# OSSIBeacon.net
KiCad netlist of a schematic drawn in EAGLE
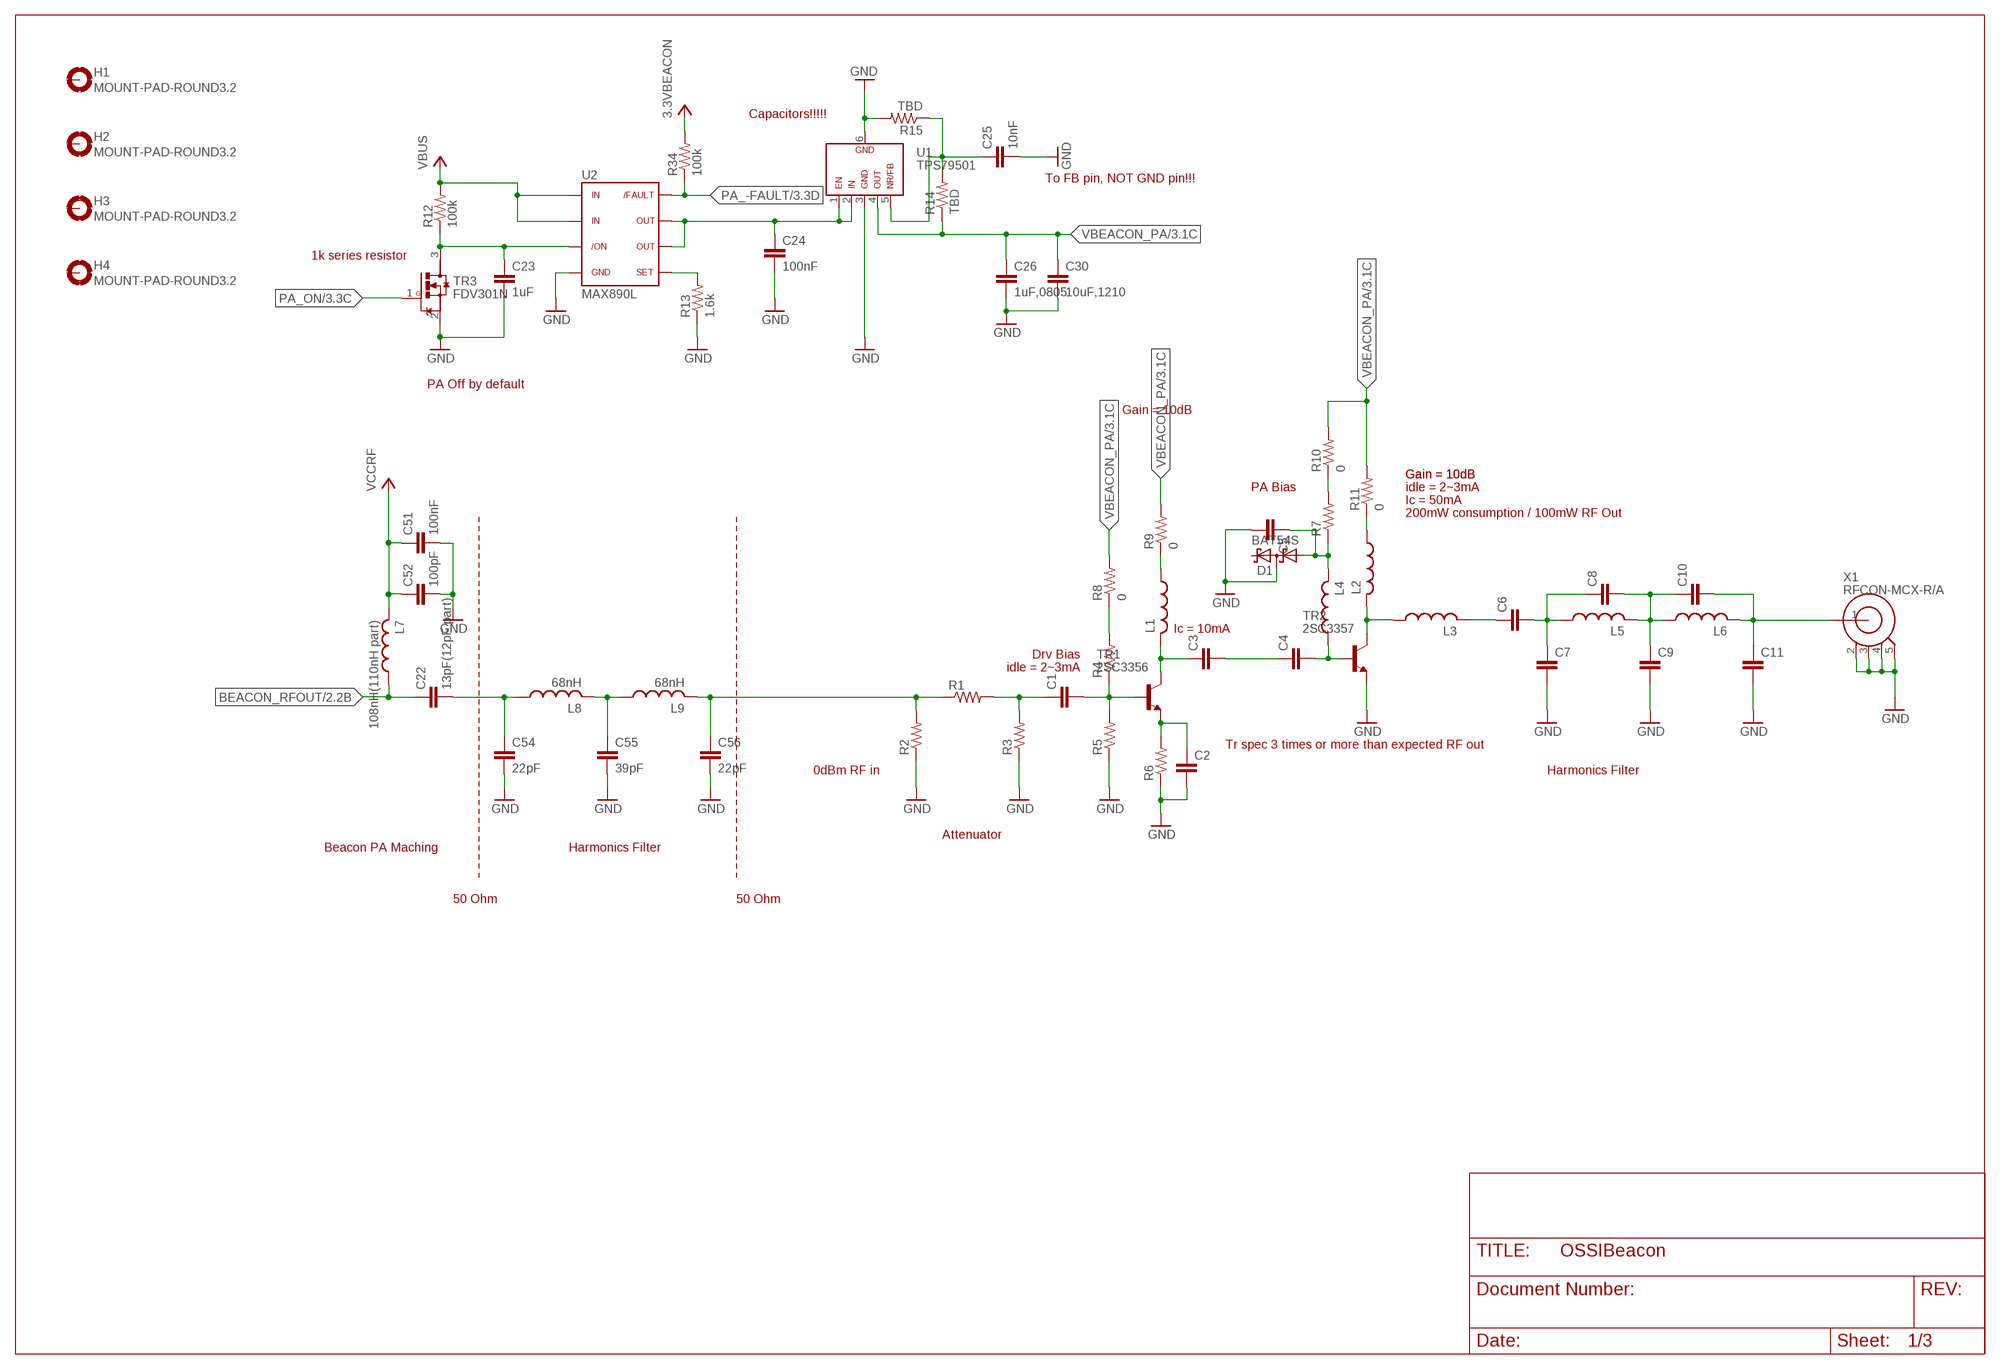
[diagram p0: schematic, sheet 1]
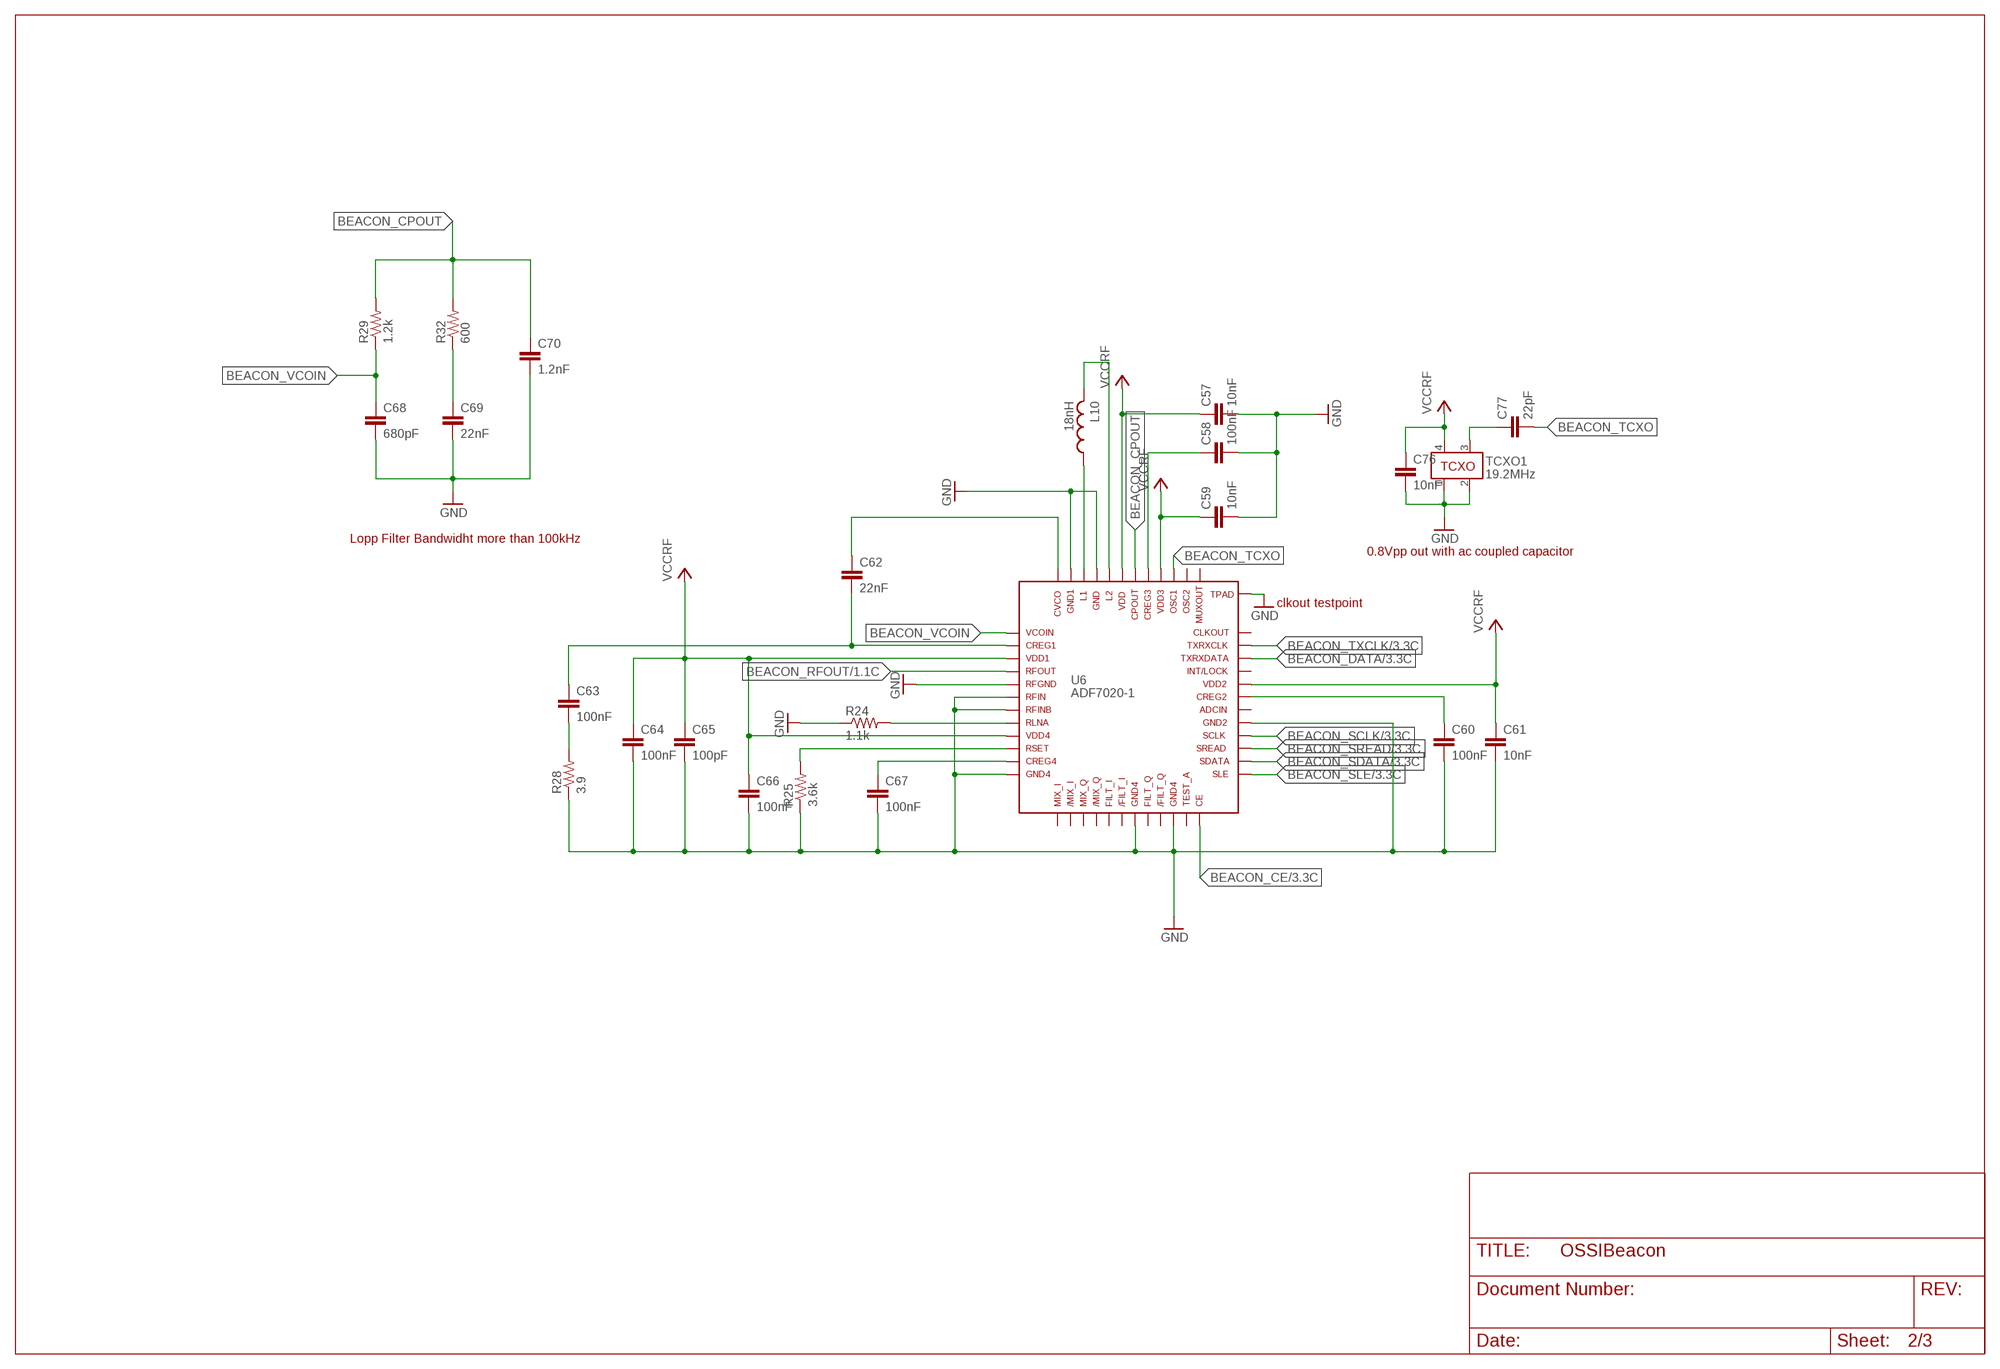
[diagram p1: schematic, sheet 2]
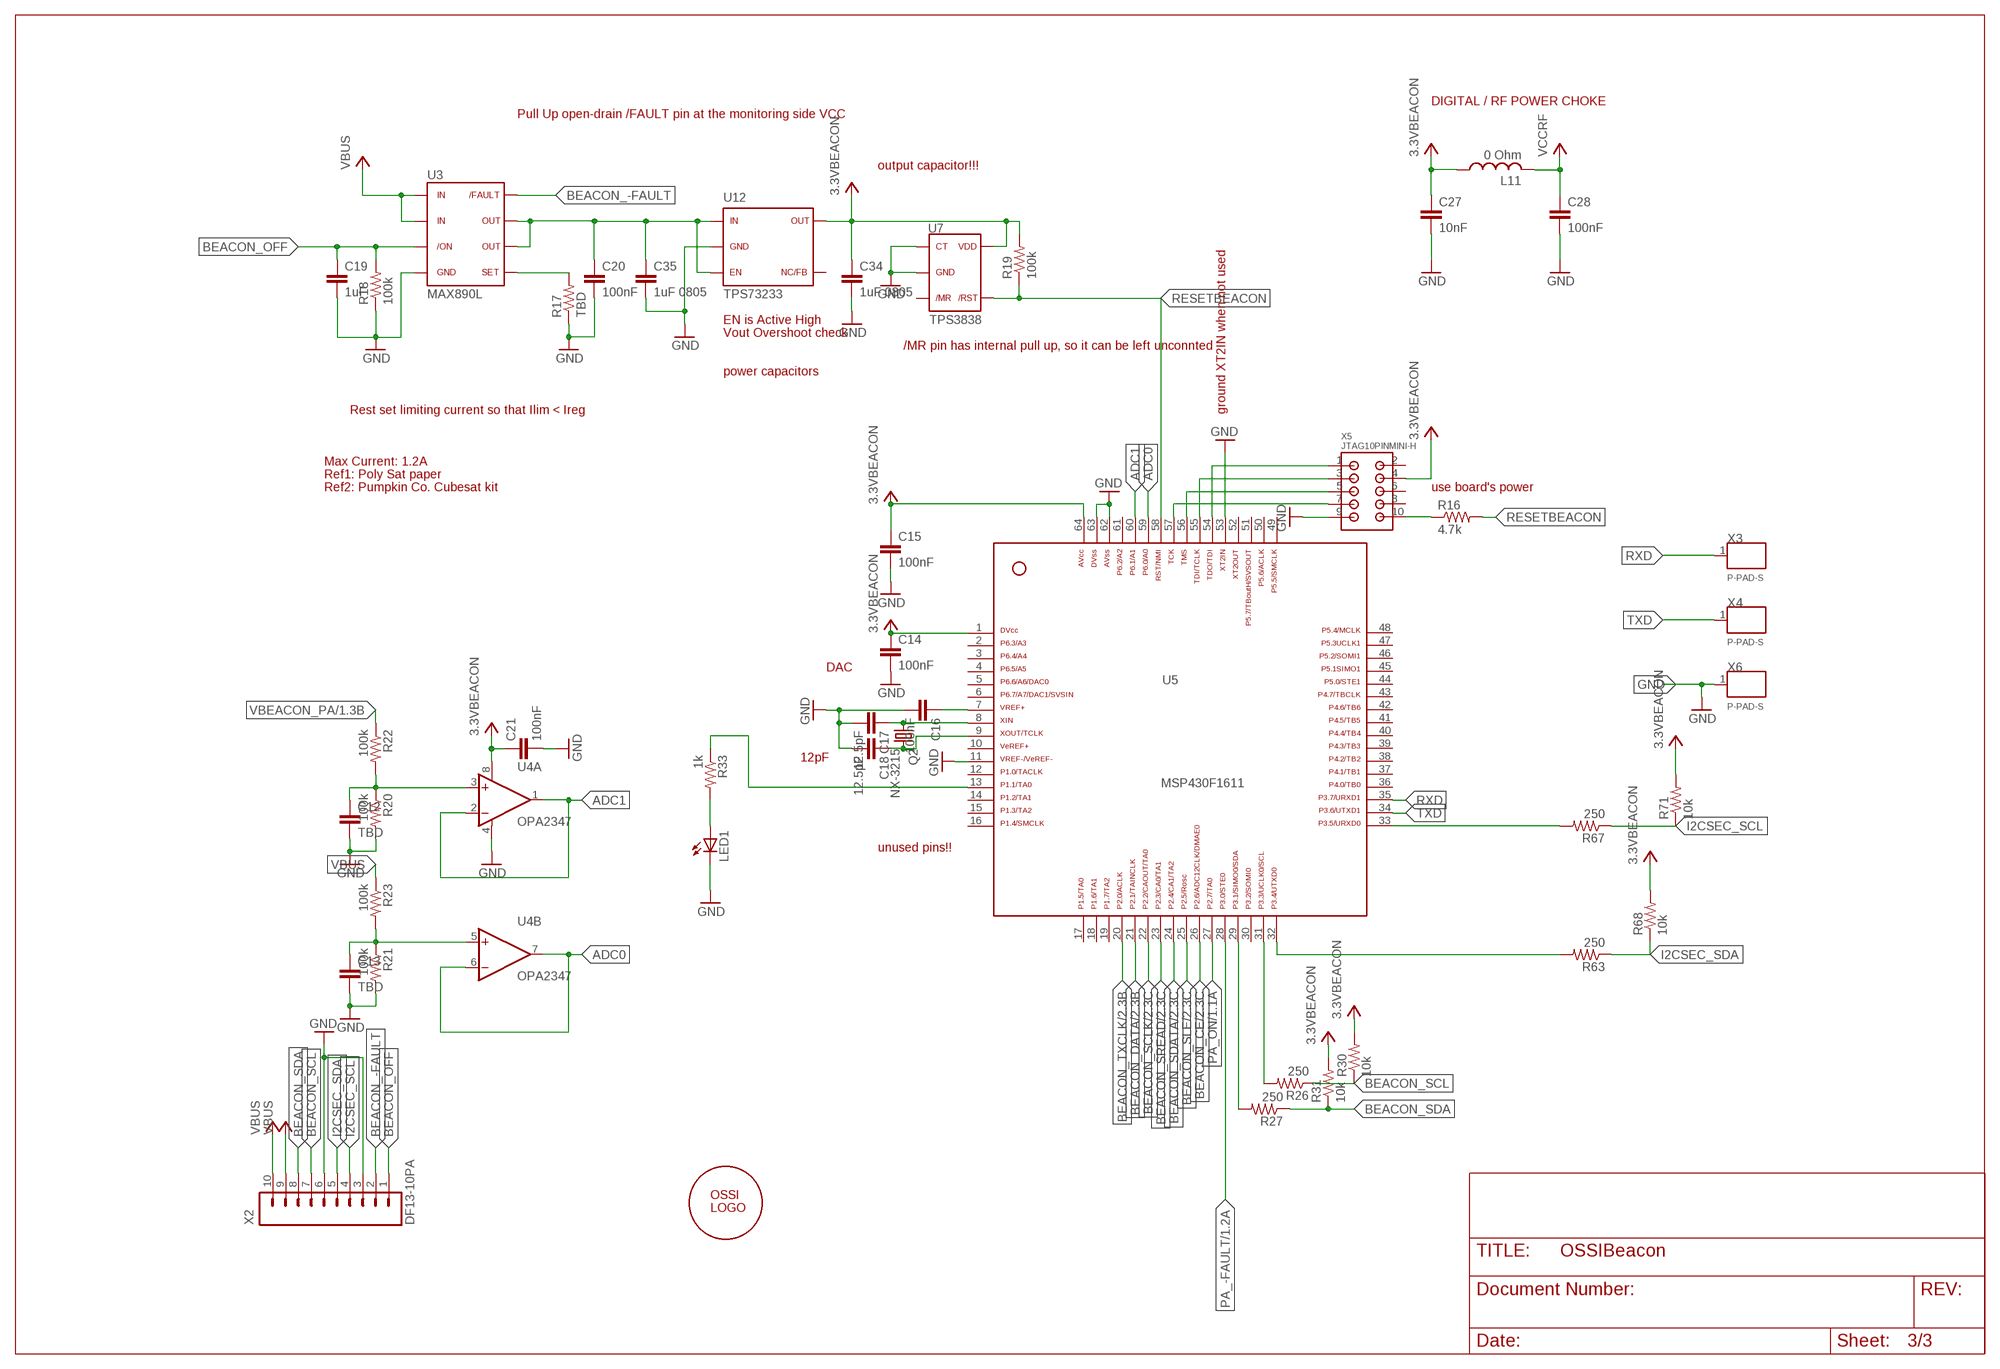
[diagram p2: schematic, sheet 3]

(export (version "E")
  (design (tool "Eeschema 10.0.6"))
  (components
    (comp (ref "C57")
      (value "10nF")
      (footprint "eagle-import:C0603(1608)")
      (libsource (lib "eagle-import") (part "C0603(1608)"))
    )
    (comp (ref "C58")
      (value "100nF")
      (footprint "eagle-import:C0603(1608)")
      (libsource (lib "eagle-import") (part "C0603(1608)"))
    )
    (comp (ref "C59")
      (value "10nF")
      (footprint "eagle-import:C0603(1608)")
      (libsource (lib "eagle-import") (part "C0603(1608)"))
    )
    (comp (ref "C60")
      (value "100nF")
      (footprint "eagle-import:C0603(1608)")
      (libsource (lib "eagle-import") (part "C0603(1608)"))
    )
    (comp (ref "C61")
      (value "10nF")
      (footprint "eagle-import:C0603(1608)")
      (libsource (lib "eagle-import") (part "C0603(1608)"))
    )
    (comp (ref "C62")
      (value "22nF")
      (footprint "eagle-import:C0603(1608)")
      (libsource (lib "eagle-import") (part "C0603(1608)"))
    )
    (comp (ref "C63")
      (value "100nF")
      (footprint "eagle-import:C0603(1608)")
      (libsource (lib "eagle-import") (part "C0603(1608)"))
    )
    (comp (ref "C64")
      (value "100nF")
      (footprint "eagle-import:C0603(1608)")
      (libsource (lib "eagle-import") (part "C0603(1608)"))
    )
    (comp (ref "C65")
      (value "100pF")
      (footprint "eagle-import:C0603(1608)")
      (libsource (lib "eagle-import") (part "C0603(1608)"))
    )
    (comp (ref "C66")
      (value "100nF")
      (footprint "eagle-import:C0603(1608)")
      (libsource (lib "eagle-import") (part "C0603(1608)"))
    )
    (comp (ref "C67")
      (value "100nF")
      (footprint "eagle-import:C0603(1608)")
      (libsource (lib "eagle-import") (part "C0603(1608)"))
    )
    (comp (ref "C68")
      (value "680pF")
      (footprint "eagle-import:C0603(1608)")
      (libsource (lib "eagle-import") (part "C0603(1608)"))
    )
    (comp (ref "C69")
      (value "22nF")
      (footprint "eagle-import:C0603(1608)")
      (libsource (lib "eagle-import") (part "C0603(1608)"))
    )
    (comp (ref "C70")
      (value "1.2nF")
      (footprint "eagle-import:C0603(1608)")
      (libsource (lib "eagle-import") (part "C0603(1608)"))
    )
    (comp (ref "C76")
      (value "10nF")
      (footprint "eagle-import:C0603(1608)")
      (libsource (lib "eagle-import") (part "C0603(1608)"))
    )
    (comp (ref "C77")
      (value "22pF")
      (footprint "eagle-import:C0603(1608)")
      (libsource (lib "eagle-import") (part "C0603(1608)"))
    )
    (comp (ref "L10")
      (value "18nH")
      (footprint "eagle-import:L0603(1608)")
      (libsource (lib "eagle-import") (part "L0603(1608)"))
    )
    (comp (ref "R24")
      (value "1.1k")
      (footprint "eagle-import:R0603(1608)")
      (libsource (lib "eagle-import") (part "R0603(1608)"))
    )
    (comp (ref "R25")
      (value "3.6k")
      (footprint "eagle-import:R0603(1608)")
      (libsource (lib "eagle-import") (part "R0603(1608)"))
    )
    (comp (ref "R28")
      (value "3.9")
      (footprint "eagle-import:R0603(1608)")
      (libsource (lib "eagle-import") (part "R0603(1608)"))
    )
    (comp (ref "R29")
      (value "1.2k")
      (footprint "eagle-import:R0603(1608)")
      (libsource (lib "eagle-import") (part "R0603(1608)"))
    )
    (comp (ref "R32")
      (value "600")
      (footprint "eagle-import:R0603(1608)")
      (libsource (lib "eagle-import") (part "R0603(1608)"))
    )
    (comp (ref "TCXO1")
      (value "19.2MHz")
      (footprint "eagle-import:TCXO_M532")
      (libsource (lib "eagle-import") (part "TCXO-M532"))
    )
    (comp (ref "U6")
      (value "ADF7020-1")
      (footprint "eagle-import:LFCSP48")
      (libsource (lib "eagle-import") (part "ADF7020-1"))
    )
    (comp (ref "C1")
      (value "C0603(1608)")
      (footprint "eagle-import:C0603(1608)")
      (libsource (lib "eagle-import") (part "C0603(1608)"))
    )
    (comp (ref "C2")
      (value "C0603(1608)")
      (footprint "eagle-import:C0603(1608)")
      (libsource (lib "eagle-import") (part "C0603(1608)"))
    )
    (comp (ref "C3")
      (value "C0603(1608)")
      (footprint "eagle-import:C0603(1608)")
      (libsource (lib "eagle-import") (part "C0603(1608)"))
    )
    (comp (ref "C4")
      (value "C0603(1608)")
      (footprint "eagle-import:C0603(1608)")
      (libsource (lib "eagle-import") (part "C0603(1608)"))
    )
    (comp (ref "C5")
      (value "C0603(1608)")
      (footprint "eagle-import:C0603(1608)")
      (libsource (lib "eagle-import") (part "C0603(1608)"))
    )
    (comp (ref "C6")
      (value "C0603(1608)")
      (footprint "eagle-import:C0603(1608)")
      (libsource (lib "eagle-import") (part "C0603(1608)"))
    )
    (comp (ref "C7")
      (value "C0603(1608)")
      (footprint "eagle-import:C0603(1608)")
      (libsource (lib "eagle-import") (part "C0603(1608)"))
    )
    (comp (ref "C8")
      (value "C0603(1608)")
      (footprint "eagle-import:C0603(1608)")
      (libsource (lib "eagle-import") (part "C0603(1608)"))
    )
    (comp (ref "C9")
      (value "C0603(1608)")
      (footprint "eagle-import:C0603(1608)")
      (libsource (lib "eagle-import") (part "C0603(1608)"))
    )
    (comp (ref "C10")
      (value "C0603(1608)")
      (footprint "eagle-import:C0603(1608)")
      (libsource (lib "eagle-import") (part "C0603(1608)"))
    )
    (comp (ref "C11")
      (value "C0603(1608)")
      (footprint "eagle-import:C0603(1608)")
      (libsource (lib "eagle-import") (part "C0603(1608)"))
    )
    (comp (ref "C22")
      (value "13pF(12pF part)")
      (footprint "eagle-import:C0603(1608)")
      (libsource (lib "eagle-import") (part "C0603(1608)"))
    )
    (comp (ref "C23")
      (value "1uF")
      (footprint "eagle-import:C0603(1608)")
      (libsource (lib "eagle-import") (part "C0603(1608)"))
    )
    (comp (ref "C24")
      (value "100nF")
      (footprint "eagle-import:C0603(1608)")
      (libsource (lib "eagle-import") (part "C0603(1608)"))
    )
    (comp (ref "C25")
      (value "10nF")
      (footprint "eagle-import:C0603(1608)")
      (libsource (lib "eagle-import") (part "C0603(1608)"))
    )
    (comp (ref "C26")
      (value "1uF,0805")
      (footprint "eagle-import:C0805(2012)")
      (libsource (lib "eagle-import") (part "C0805(2012)"))
    )
    (comp (ref "C30")
      (value "10uF,1210")
      (footprint "eagle-import:C1210-GCM32")
      (libsource (lib "eagle-import") (part "C1210(3225)-GCM32"))
    )
    (comp (ref "C51")
      (value "100nF")
      (footprint "eagle-import:C0603(1608)")
      (libsource (lib "eagle-import") (part "C0603(1608)"))
    )
    (comp (ref "C52")
      (value "100pF")
      (footprint "eagle-import:C0603(1608)")
      (libsource (lib "eagle-import") (part "C0603(1608)"))
    )
    (comp (ref "C54")
      (value "22pF")
      (footprint "eagle-import:C0603(1608)")
      (libsource (lib "eagle-import") (part "C0603(1608)"))
    )
    (comp (ref "C55")
      (value "39pF")
      (footprint "eagle-import:C0603(1608)")
      (libsource (lib "eagle-import") (part "C0603(1608)"))
    )
    (comp (ref "C56")
      (value "22pF")
      (footprint "eagle-import:C0603(1608)")
      (libsource (lib "eagle-import") (part "C0603(1608)"))
    )
    (comp (ref "D1")
      (value "BAT54S")
      (footprint "eagle-import:SOT23")
      (libsource (lib "eagle-import") (part "BAT54S"))
    )
    (comp (ref "H1")
      (value "MOUNT-PAD-ROUND3.2")
      (footprint "eagle-import:3.2-PAD-ROUND")
      (libsource (lib "eagle-import") (part "MOUNT-PAD-ROUND3.2"))
    )
    (comp (ref "H2")
      (value "MOUNT-PAD-ROUND3.2")
      (footprint "eagle-import:3.2-PAD-ROUND")
      (libsource (lib "eagle-import") (part "MOUNT-PAD-ROUND3.2"))
    )
    (comp (ref "H3")
      (value "MOUNT-PAD-ROUND3.2")
      (footprint "eagle-import:3.2-PAD-ROUND")
      (libsource (lib "eagle-import") (part "MOUNT-PAD-ROUND3.2"))
    )
    (comp (ref "H4")
      (value "MOUNT-PAD-ROUND3.2")
      (footprint "eagle-import:3.2-PAD-ROUND")
      (libsource (lib "eagle-import") (part "MOUNT-PAD-ROUND3.2"))
    )
    (comp (ref "L1")
      (value "L1008(2502)")
      (footprint "eagle-import:L1008(2520)")
      (libsource (lib "eagle-import") (part "L1008(2502)"))
    )
    (comp (ref "L2")
      (value "L1008(2502)")
      (footprint "eagle-import:L1008(2520)")
      (libsource (lib "eagle-import") (part "L1008(2502)"))
    )
    (comp (ref "L3")
      (value "L0603(1608)")
      (footprint "eagle-import:L0603(1608)")
      (libsource (lib "eagle-import") (part "L0603(1608)"))
    )
    (comp (ref "L4")
      (value "L0603(1608)")
      (footprint "eagle-import:L0603(1608)")
      (libsource (lib "eagle-import") (part "L0603(1608)"))
    )
    (comp (ref "L5")
      (value "L0603(1608)")
      (footprint "eagle-import:L0603(1608)")
      (libsource (lib "eagle-import") (part "L0603(1608)"))
    )
    (comp (ref "L6")
      (value "L0603(1608)")
      (footprint "eagle-import:L0603(1608)")
      (libsource (lib "eagle-import") (part "L0603(1608)"))
    )
    (comp (ref "L7")
      (value "108nH(110nH part)")
      (footprint "eagle-import:L0603(1608)")
      (libsource (lib "eagle-import") (part "L0603(1608)"))
    )
    (comp (ref "L8")
      (value "68nH")
      (footprint "eagle-import:L0603(1608)")
      (libsource (lib "eagle-import") (part "L0603(1608)"))
    )
    (comp (ref "L9")
      (value "68nH")
      (footprint "eagle-import:L0603(1608)")
      (libsource (lib "eagle-import") (part "L0603(1608)"))
    )
    (comp (ref "R1")
      (value "R0603(1608)")
      (footprint "eagle-import:R0603(1608)")
      (libsource (lib "eagle-import") (part "R0603(1608)"))
    )
    (comp (ref "R2")
      (value "R0603(1608)")
      (footprint "eagle-import:R0603(1608)")
      (libsource (lib "eagle-import") (part "R0603(1608)"))
    )
    (comp (ref "R3")
      (value "R0603(1608)")
      (footprint "eagle-import:R0603(1608)")
      (libsource (lib "eagle-import") (part "R0603(1608)"))
    )
    (comp (ref "R4")
      (value "R0603(1608)")
      (footprint "eagle-import:R0603(1608)")
      (libsource (lib "eagle-import") (part "R0603(1608)"))
    )
    (comp (ref "R5")
      (value "R0603(1608)")
      (footprint "eagle-import:R0603(1608)")
      (libsource (lib "eagle-import") (part "R0603(1608)"))
    )
    (comp (ref "R6")
      (value "R0603(1608)")
      (footprint "eagle-import:R0603(1608)")
      (libsource (lib "eagle-import") (part "R0603(1608)"))
    )
    (comp (ref "R7")
      (value "R0603(1608)")
      (footprint "eagle-import:R0603(1608)")
      (libsource (lib "eagle-import") (part "R0603(1608)"))
    )
    (comp (ref "R8")
      (value "0")
      (footprint "eagle-import:R0603(1608)")
      (libsource (lib "eagle-import") (part "R0603(1608)"))
    )
    (comp (ref "R9")
      (value "0")
      (footprint "eagle-import:R0603(1608)")
      (libsource (lib "eagle-import") (part "R0603(1608)"))
    )
    (comp (ref "R10")
      (value "0")
      (footprint "eagle-import:R0603(1608)")
      (libsource (lib "eagle-import") (part "R0603(1608)"))
    )
    (comp (ref "R11")
      (value "0")
      (footprint "eagle-import:R0603(1608)")
      (libsource (lib "eagle-import") (part "R0603(1608)"))
    )
    (comp (ref "R12")
      (value "100k")
      (footprint "eagle-import:R0603(1608)")
      (libsource (lib "eagle-import") (part "R0603(1608)"))
    )
    (comp (ref "R13")
      (value "1.6k")
      (footprint "eagle-import:R0603(1608)")
      (libsource (lib "eagle-import") (part "R0603(1608)"))
    )
    (comp (ref "R14")
      (value "TBD")
      (footprint "eagle-import:R0603(1608)")
      (libsource (lib "eagle-import") (part "R0603(1608)"))
    )
    (comp (ref "R15")
      (value "TBD")
      (footprint "eagle-import:R0603(1608)")
      (libsource (lib "eagle-import") (part "R0603(1608)"))
    )
    (comp (ref "R34")
      (value "100k")
      (footprint "eagle-import:R0603(1608)")
      (libsource (lib "eagle-import") (part "R0603(1608)"))
    )
    (comp (ref "TR1")
      (value "2SC3356")
      (footprint "eagle-import:SOT23-BEC")
      (libsource (lib "eagle-import") (part "2SC3356"))
    )
    (comp (ref "TR2")
      (value "2SC3357")
      (footprint "eagle-import:SOT89-R")
      (libsource (lib "eagle-import") (part "2SC3357"))
    )
    (comp (ref "TR3")
      (value "FDV301N")
      (footprint "eagle-import:SOT23")
      (libsource (lib "eagle-import") (part "FDV301N"))
    )
    (comp (ref "U1")
      (value "TPS79501")
      (footprint "eagle-import:SOT223-6")
      (libsource (lib "eagle-import") (part "TPS79501"))
    )
    (comp (ref "U2")
      (value "MAX890L")
      (footprint "eagle-import:SO8")
      (libsource (lib "eagle-import") (part "MAX890L"))
    )
    (comp (ref "X1")
      (value "RFCON-MCX-R/A")
      (footprint "eagle-import:MCX-R_A")
      (libsource (lib "eagle-import") (part "RFCON-MCX-R/A"))
    )
    (comp (ref "C12")
      (value "TBD")
      (footprint "eagle-import:C0603(1608)")
      (libsource (lib "eagle-import") (part "C0603(1608)"))
    )
    (comp (ref "C13")
      (value "TBD")
      (footprint "eagle-import:C0603(1608)")
      (libsource (lib "eagle-import") (part "C0603(1608)"))
    )
    (comp (ref "C14")
      (value "100nF")
      (footprint "eagle-import:C0603(1608)")
      (libsource (lib "eagle-import") (part "C0603(1608)"))
    )
    (comp (ref "C15")
      (value "100nF")
      (footprint "eagle-import:C0603(1608)")
      (libsource (lib "eagle-import") (part "C0603(1608)"))
    )
    (comp (ref "C16")
      (value "100nF")
      (footprint "eagle-import:C0603(1608)")
      (libsource (lib "eagle-import") (part "C0603(1608)"))
    )
    (comp (ref "C17")
      (value "12.5pF")
      (footprint "eagle-import:C0603(1608)")
      (libsource (lib "eagle-import") (part "C0603(1608)"))
    )
    (comp (ref "C18")
      (value "12.5pF")
      (footprint "eagle-import:C0603(1608)")
      (libsource (lib "eagle-import") (part "C0603(1608)"))
    )
    (comp (ref "C19")
      (value "1uF")
      (footprint "eagle-import:C0603(1608)")
      (libsource (lib "eagle-import") (part "C0603(1608)"))
    )
    (comp (ref "C20")
      (value "100nF")
      (footprint "eagle-import:C0603(1608)")
      (libsource (lib "eagle-import") (part "C0603(1608)"))
    )
    (comp (ref "C21")
      (value "100nF")
      (footprint "eagle-import:C0603(1608)")
      (libsource (lib "eagle-import") (part "C0603(1608)"))
    )
    (comp (ref "C27")
      (value "10nF")
      (footprint "eagle-import:C0603(1608)")
      (libsource (lib "eagle-import") (part "C0603(1608)"))
    )
    (comp (ref "C28")
      (value "100nF")
      (footprint "eagle-import:C0603(1608)")
      (libsource (lib "eagle-import") (part "C0603(1608)"))
    )
    (comp (ref "C34")
      (value "1uF 0805")
      (footprint "eagle-import:C0805(2012)")
      (libsource (lib "eagle-import") (part "C0805(2012)"))
    )
    (comp (ref "C35")
      (value "1uF 0805")
      (footprint "eagle-import:C0805(2012)")
      (libsource (lib "eagle-import") (part "C0805(2012)"))
    )
    (comp (ref "L11")
      (value "0 Ohm")
      (footprint "eagle-import:L0805(2012)")
      (libsource (lib "eagle-import") (part "L0805(2012)"))
    )
    (comp (ref "LED1")
      (value "LED0603")
      (footprint "eagle-import:LED-0603")
      (libsource (lib "eagle-import") (part "LED0603"))
    )
    (comp (ref "Q2")
      (value "NX-3215")
      (footprint "eagle-import:NX-3215")
      (libsource (lib "eagle-import") (part "NX-3215"))
    )
    (comp (ref "R16")
      (value "4.7k")
      (footprint "eagle-import:R0603(1608)")
      (libsource (lib "eagle-import") (part "R0603(1608)"))
    )
    (comp (ref "R17")
      (value "TBD")
      (footprint "eagle-import:R0603(1608)")
      (libsource (lib "eagle-import") (part "R0603(1608)"))
    )
    (comp (ref "R18")
      (value "100k")
      (footprint "eagle-import:R0603(1608)")
      (libsource (lib "eagle-import") (part "R0603(1608)"))
    )
    (comp (ref "R19")
      (value "100k")
      (footprint "eagle-import:R0603(1608)")
      (libsource (lib "eagle-import") (part "R0603(1608)"))
    )
    (comp (ref "R20")
      (value "100k")
      (footprint "eagle-import:R0603(1608)")
      (libsource (lib "eagle-import") (part "R0603(1608)"))
    )
    (comp (ref "R21")
      (value "100k")
      (footprint "eagle-import:R0603(1608)")
      (libsource (lib "eagle-import") (part "R0603(1608)"))
    )
    (comp (ref "R22")
      (value "100k")
      (footprint "eagle-import:R0603(1608)")
      (libsource (lib "eagle-import") (part "R0603(1608)"))
    )
    (comp (ref "R23")
      (value "100k")
      (footprint "eagle-import:R0603(1608)")
      (libsource (lib "eagle-import") (part "R0603(1608)"))
    )
    (comp (ref "R26")
      (value "250")
      (footprint "eagle-import:R0603(1608)")
      (libsource (lib "eagle-import") (part "R0603(1608)"))
    )
    (comp (ref "R27")
      (value "250")
      (footprint "eagle-import:R0603(1608)")
      (libsource (lib "eagle-import") (part "R0603(1608)"))
    )
    (comp (ref "R30")
      (value "10k")
      (footprint "eagle-import:R0603(1608)")
      (libsource (lib "eagle-import") (part "R0603(1608)"))
    )
    (comp (ref "R31")
      (value "10k")
      (footprint "eagle-import:R0603(1608)")
      (libsource (lib "eagle-import") (part "R0603(1608)"))
    )
    (comp (ref "R33")
      (value "1k")
      (footprint "eagle-import:R0603(1608)")
      (libsource (lib "eagle-import") (part "R0603(1608)"))
    )
    (comp (ref "R63")
      (value "250")
      (footprint "eagle-import:R0603(1608)")
      (libsource (lib "eagle-import") (part "R0603(1608)"))
    )
    (comp (ref "R67")
      (value "250")
      (footprint "eagle-import:R0603(1608)")
      (libsource (lib "eagle-import") (part "R0603(1608)"))
    )
    (comp (ref "R68")
      (value "10k")
      (footprint "eagle-import:R0603(1608)")
      (libsource (lib "eagle-import") (part "R0603(1608)"))
    )
    (comp (ref "R71")
      (value "10k")
      (footprint "eagle-import:R0603(1608)")
      (libsource (lib "eagle-import") (part "R0603(1608)"))
    )
    (comp (ref "U$1")
      (value "OSSILOGORECT")
      (footprint "eagle-import:OSSILOGORECT1005")
      (libsource (lib "eagle-import") (part "OSSILOGORECT"))
    )
    (comp (ref "U3")
      (value "MAX890L")
      (footprint "eagle-import:SO8")
      (libsource (lib "eagle-import") (part "MAX890L"))
    )
    (comp (ref "U4")
      (value "OPA2347")
      (footprint "eagle-import:SOT23-8DCN")
      (libsource (lib "eagle-import") (part "OPA2347"))
    )
    (comp (ref "U5")
      (value "MSP430F1611")
      (footprint "eagle-import:PM_PAG64")
      (libsource (lib "eagle-import") (part "MSP430F1611"))
    )
    (comp (ref "U7")
      (value "TPS3838")
      (footprint "eagle-import:SOT23-5DBV")
      (libsource (lib "eagle-import") (part "TPS3838"))
    )
    (comp (ref "U12")
      (value "TPS73233")
      (footprint "eagle-import:SOT23-5DBV")
      (libsource (lib "eagle-import") (part "TPS73233"))
    )
    (comp (ref "X2")
      (value "DF13-10PA")
      (footprint "eagle-import:DF13A-10P")
      (libsource (lib "eagle-import") (part "DF13-10PA"))
    )
    (comp (ref "X3")
      (value "P-PAD-S")
      (footprint "eagle-import:P-PAD-S")
      (libsource (lib "eagle-import") (part "P-PAD-S"))
    )
    (comp (ref "X4")
      (value "P-PAD-S")
      (footprint "eagle-import:P-PAD-S")
      (libsource (lib "eagle-import") (part "P-PAD-S"))
    )
    (comp (ref "X5")
      (value "JTAG10PINMINI-H")
      (footprint "eagle-import:M50-3200545")
      (libsource (lib "eagle-import") (part "JTAG10PINMINI-H"))
    )
    (comp (ref "X6")
      (value "P-PAD-S")
      (footprint "eagle-import:P-PAD-S")
      (libsource (lib "eagle-import") (part "P-PAD-S"))
    )
  )
  (nets
    (net (code "1") (name "3.3VBEACON") (class "Default")
      (node (ref "C14") (pin "1") (pinfunction "1_1") (pintype "passive"))
      (node (ref "C15") (pin "1") (pinfunction "1_1") (pintype "passive"))
      (node (ref "C21") (pin "1") (pinfunction "1_1") (pintype "passive"))
      (node (ref "C27") (pin "1") (pinfunction "1_1") (pintype "passive"))
      (node (ref "C34") (pin "1") (pinfunction "1_1") (pintype "passive"))
      (node (ref "L11") (pin "1") (pinfunction "1_1") (pintype "passive"))
      (node (ref "R19") (pin "2") (pinfunction "2_2") (pintype "passive"))
      (node (ref "R30") (pin "2") (pinfunction "2_2") (pintype "passive"))
      (node (ref "R31") (pin "2") (pinfunction "2_2") (pintype "passive"))
      (node (ref "R34") (pin "2") (pinfunction "2_2") (pintype "passive"))
      (node (ref "R68") (pin "2") (pinfunction "2_2") (pintype "passive"))
      (node (ref "R71") (pin "2") (pinfunction "2_2") (pintype "passive"))
      (node (ref "U12") (pin "5") (pinfunction "5_5") (pintype "power_in"))
      (node (ref "U4") (pin "8") (pinfunction "V+_8") (pintype "power_in"))
      (node (ref "U5") (pin "1") (pinfunction "1_1") (pintype "power_in"))
      (node (ref "U5") (pin "64") (pinfunction "64_64") (pintype "power_in"))
      (node (ref "U7") (pin "5") (pinfunction "P$5_5") (pintype "power_in"))
      (node (ref "X5") (pin "4") (pinfunction "4_4") (pintype "bidirectional"))
    )
    (net (code "2") (name "ADC0") (class "Default")
      (node (ref "U4") (pin "6") (pinfunction "-IN_6") (pintype "input"))
      (node (ref "U4") (pin "7") (pinfunction "OUT_7") (pintype "output"))
      (node (ref "U5") (pin "59") (pinfunction "59_59") (pintype "bidirectional"))
    )
    (net (code "3") (name "ADC1") (class "Default")
      (node (ref "U4") (pin "1") (pinfunction "OUT_1") (pintype "output"))
      (node (ref "U4") (pin "2") (pinfunction "-IN_2") (pintype "input"))
      (node (ref "U5") (pin "60") (pinfunction "60_60") (pintype "bidirectional"))
    )
    (net (code "4") (name "BEACON_-FAULT") (class "Default")
      (node (ref "U3") (pin "8") (pinfunction "P$8_8") (pintype "output"))
      (node (ref "X2") (pin "2") (pinfunction "2_2") (pintype "passive"))
    )
    (net (code "5") (name "BEACON_CE") (class "Default")
      (node (ref "U5") (pin "26") (pinfunction "26_26") (pintype "bidirectional"))
      (node (ref "U6") (pin "24") (pinfunction "P$24_24") (pintype "bidirectional"))
    )
    (net (code "6") (name "BEACON_CPOUT") (class "Default")
      (node (ref "C70") (pin "1") (pinfunction "1_1") (pintype "passive"))
      (node (ref "R29") (pin "2") (pinfunction "2_2") (pintype "passive"))
      (node (ref "R32") (pin "2") (pinfunction "2_2") (pintype "passive"))
      (node (ref "U6") (pin "42") (pinfunction "P$42_42") (pintype "bidirectional"))
    )
    (net (code "7") (name "BEACON_DATA") (class "Default")
      (node (ref "U5") (pin "21") (pinfunction "21_21") (pintype "bidirectional"))
      (node (ref "U6") (pin "34") (pinfunction "P$34_34") (pintype "bidirectional"))
    )
    (net (code "8") (name "BEACON_OFF") (class "Default")
      (node (ref "C19") (pin "1") (pinfunction "1_1") (pintype "passive"))
      (node (ref "R18") (pin "2") (pinfunction "2_2") (pintype "passive"))
      (node (ref "U3") (pin "3") (pinfunction "P$3_3") (pintype "input"))
      (node (ref "X2") (pin "1") (pinfunction "1_1") (pintype "passive"))
    )
    (net (code "9") (name "BEACON_RFOUT") (class "Default")
      (node (ref "C22") (pin "1") (pinfunction "1_1") (pintype "passive"))
      (node (ref "L7") (pin "1") (pinfunction "1_1") (pintype "passive"))
      (node (ref "U6") (pin "4") (pinfunction "P$4_4") (pintype "bidirectional"))
    )
    (net (code "10") (name "BEACON_SCL") (class "Default")
      (node (ref "R26") (pin "1") (pinfunction "1_1") (pintype "passive"))
      (node (ref "R30") (pin "1") (pinfunction "1_1") (pintype "passive"))
      (node (ref "X2") (pin "7") (pinfunction "7_7") (pintype "passive"))
    )
    (net (code "11") (name "BEACON_SCLK") (class "Default")
      (node (ref "U5") (pin "22") (pinfunction "22_22") (pintype "bidirectional"))
      (node (ref "U6") (pin "28") (pinfunction "P$28_28") (pintype "bidirectional"))
    )
    (net (code "12") (name "BEACON_SDA") (class "Default")
      (node (ref "R27") (pin "1") (pinfunction "1_1") (pintype "passive"))
      (node (ref "R31") (pin "1") (pinfunction "1_1") (pintype "passive"))
      (node (ref "X2") (pin "8") (pinfunction "8_8") (pintype "passive"))
    )
    (net (code "13") (name "BEACON_SDATA") (class "Default")
      (node (ref "U5") (pin "24") (pinfunction "24_24") (pintype "bidirectional"))
      (node (ref "U6") (pin "26") (pinfunction "P$26_26") (pintype "bidirectional"))
    )
    (net (code "14") (name "BEACON_SLE") (class "Default")
      (node (ref "U5") (pin "25") (pinfunction "25_25") (pintype "bidirectional"))
      (node (ref "U6") (pin "25") (pinfunction "P$25_25") (pintype "bidirectional"))
    )
    (net (code "15") (name "BEACON_SREAD") (class "Default")
      (node (ref "U5") (pin "23") (pinfunction "23_23") (pintype "bidirectional"))
      (node (ref "U6") (pin "27") (pinfunction "P$27_27") (pintype "bidirectional"))
    )
    (net (code "16") (name "BEACON_TCXO") (class "Default")
      (node (ref "C77") (pin "2") (pinfunction "2_2") (pintype "passive"))
      (node (ref "U6") (pin "39") (pinfunction "P$39_39") (pintype "bidirectional"))
    )
    (net (code "17") (name "BEACON_TXCLK") (class "Default")
      (node (ref "U5") (pin "20") (pinfunction "20_20") (pintype "bidirectional"))
      (node (ref "U6") (pin "35") (pinfunction "P$35_35") (pintype "bidirectional"))
    )
    (net (code "18") (name "BEACON_VCOIN") (class "Default")
      (node (ref "C68") (pin "1") (pinfunction "1_1") (pintype "passive"))
      (node (ref "R29") (pin "1") (pinfunction "1_1") (pintype "passive"))
      (node (ref "U6") (pin "1") (pinfunction "P$1_1") (pintype "bidirectional"))
    )
    (net (code "19") (name "GND") (class "Default")
      (node (ref "C11") (pin "2") (pinfunction "2_2") (pintype "passive"))
      (node (ref "C12") (pin "2") (pinfunction "2_2") (pintype "passive"))
      (node (ref "C13") (pin "2") (pinfunction "2_2") (pintype "passive"))
      (node (ref "C14") (pin "2") (pinfunction "2_2") (pintype "passive"))
      (node (ref "C15") (pin "2") (pinfunction "2_2") (pintype "passive"))
      (node (ref "C16") (pin "2") (pinfunction "2_2") (pintype "passive"))
      (node (ref "C17") (pin "2") (pinfunction "2_2") (pintype "passive"))
      (node (ref "C18") (pin "2") (pinfunction "2_2") (pintype "passive"))
      (node (ref "C19") (pin "2") (pinfunction "2_2") (pintype "passive"))
      (node (ref "C2") (pin "2") (pinfunction "2_2") (pintype "passive"))
      (node (ref "C20") (pin "2") (pinfunction "2_2") (pintype "passive"))
      (node (ref "C21") (pin "2") (pinfunction "2_2") (pintype "passive"))
      (node (ref "C23") (pin "2") (pinfunction "2_2") (pintype "passive"))
      (node (ref "C24") (pin "2") (pinfunction "2_2") (pintype "passive"))
      (node (ref "C25") (pin "2") (pinfunction "2_2") (pintype "passive"))
      (node (ref "C26") (pin "2") (pinfunction "2_2") (pintype "passive"))
      (node (ref "C27") (pin "2") (pinfunction "2_2") (pintype "passive"))
      (node (ref "C28") (pin "2") (pinfunction "2_2") (pintype "passive"))
      (node (ref "C30") (pin "P$2") (pinfunction "2_P$2") (pintype "passive"))
      (node (ref "C34") (pin "2") (pinfunction "2_2") (pintype "passive"))
      (node (ref "C35") (pin "2") (pinfunction "2_2") (pintype "passive"))
      (node (ref "C5") (pin "2") (pinfunction "2_2") (pintype "passive"))
      (node (ref "C51") (pin "2") (pinfunction "2_2") (pintype "passive"))
      (node (ref "C52") (pin "2") (pinfunction "2_2") (pintype "passive"))
      (node (ref "C54") (pin "2") (pinfunction "2_2") (pintype "passive"))
      (node (ref "C55") (pin "2") (pinfunction "2_2") (pintype "passive"))
      (node (ref "C56") (pin "2") (pinfunction "2_2") (pintype "passive"))
      (node (ref "C57") (pin "2") (pinfunction "2_2") (pintype "passive"))
      (node (ref "C58") (pin "2") (pinfunction "2_2") (pintype "passive"))
      (node (ref "C59") (pin "2") (pinfunction "2_2") (pintype "passive"))
      (node (ref "C60") (pin "2") (pinfunction "2_2") (pintype "passive"))
      (node (ref "C61") (pin "2") (pinfunction "2_2") (pintype "passive"))
      (node (ref "C64") (pin "2") (pinfunction "2_2") (pintype "passive"))
      (node (ref "C65") (pin "2") (pinfunction "2_2") (pintype "passive"))
      (node (ref "C66") (pin "2") (pinfunction "2_2") (pintype "passive"))
      (node (ref "C67") (pin "2") (pinfunction "2_2") (pintype "passive"))
      (node (ref "C68") (pin "2") (pinfunction "2_2") (pintype "passive"))
      (node (ref "C69") (pin "2") (pinfunction "2_2") (pintype "passive"))
      (node (ref "C7") (pin "2") (pinfunction "2_2") (pintype "passive"))
      (node (ref "C70") (pin "2") (pinfunction "2_2") (pintype "passive"))
      (node (ref "C76") (pin "2") (pinfunction "2_2") (pintype "passive"))
      (node (ref "C9") (pin "2") (pinfunction "2_2") (pintype "passive"))
      (node (ref "D1") (pin "3") (pinfunction "C1A2_3") (pintype "passive"))
      (node (ref "LED1") (pin "C") (pinfunction "C_C") (pintype "passive"))
      (node (ref "R13") (pin "1") (pinfunction "1_1") (pintype "passive"))
      (node (ref "R15") (pin "2") (pinfunction "2_2") (pintype "passive"))
      (node (ref "R17") (pin "1") (pinfunction "1_1") (pintype "passive"))
      (node (ref "R18") (pin "1") (pinfunction "1_1") (pintype "passive"))
      (node (ref "R2") (pin "1") (pinfunction "1_1") (pintype "passive"))
      (node (ref "R20") (pin "2") (pinfunction "2_2") (pintype "passive"))
      (node (ref "R21") (pin "2") (pinfunction "2_2") (pintype "passive"))
      (node (ref "R24") (pin "1") (pinfunction "1_1") (pintype "passive"))
      (node (ref "R25") (pin "1") (pinfunction "1_1") (pintype "passive"))
      (node (ref "R28") (pin "1") (pinfunction "1_1") (pintype "passive"))
      (node (ref "R3") (pin "1") (pinfunction "1_1") (pintype "passive"))
      (node (ref "R5") (pin "1") (pinfunction "1_1") (pintype "passive"))
      (node (ref "R6") (pin "1") (pinfunction "1_1") (pintype "passive"))
      (node (ref "TCXO1") (pin "1") (pinfunction "P$1_1") (pintype "bidirectional"))
      (node (ref "TCXO1") (pin "2") (pinfunction "P$2_2") (pintype "bidirectional"))
      (node (ref "TR2") (pin "E") (pinfunction "E_E") (pintype "passive"))
      (node (ref "TR3") (pin "2") (pinfunction "S_2") (pintype "bidirectional"))
      (node (ref "U1") (pin "3") (pinfunction "P$3_3") (pintype "power_in"))
      (node (ref "U1") (pin "6") (pinfunction "P$6_6") (pintype "power_in"))
      (node (ref "U12") (pin "2") (pinfunction "2_2") (pintype "power_in"))
      (node (ref "U2") (pin "4") (pinfunction "P$4_4") (pintype "power_in"))
      (node (ref "U3") (pin "4") (pinfunction "P$4_4") (pintype "power_in"))
      (node (ref "U4") (pin "4") (pinfunction "V-_4") (pintype "power_in"))
      (node (ref "U5") (pin "11") (pinfunction "11_11") (pintype "bidirectional"))
      (node (ref "U5") (pin "53") (pinfunction "53_53") (pintype "input"))
      (node (ref "U5") (pin "62") (pinfunction "62_62") (pintype "power_in"))
      (node (ref "U5") (pin "63") (pinfunction "63_63") (pintype "power_in"))
      (node (ref "U6") (pin "12") (pinfunction "P$12_12") (pintype "bidirectional"))
      (node (ref "U6") (pin "19") (pinfunction "P$19_19") (pintype "bidirectional"))
      (node (ref "U6") (pin "22") (pinfunction "P$22_22") (pintype "bidirectional"))
      (node (ref "U6") (pin "29") (pinfunction "P$29_29") (pintype "bidirectional"))
      (node (ref "U6") (pin "45") (pinfunction "P$45_45") (pintype "bidirectional"))
      (node (ref "U6") (pin "47") (pinfunction "P$47_47") (pintype "bidirectional"))
      (node (ref "U6") (pin "5") (pinfunction "P$5_5") (pintype "bidirectional"))
      (node (ref "U6") (pin "6") (pinfunction "P$6_6") (pintype "bidirectional"))
      (node (ref "U6") (pin "7") (pinfunction "P$7_7") (pintype "bidirectional"))
      (node (ref "U6") (pin "EXP") (pinfunction "P$49_EXP") (pintype "bidirectional"))
      (node (ref "U7") (pin "1") (pinfunction "P$1_1") (pintype "bidirectional"))
      (node (ref "U7") (pin "2") (pinfunction "P$2_2") (pintype "power_in"))
      (node (ref "X1") (pin "2") (pinfunction "2_2") (pintype "power_in"))
      (node (ref "X1") (pin "3") (pinfunction "3_3") (pintype "power_in"))
      (node (ref "X1") (pin "4") (pinfunction "4_4") (pintype "power_in"))
      (node (ref "X1") (pin "5") (pinfunction "5_5") (pintype "power_in"))
      (node (ref "X2") (pin "3") (pinfunction "3_3") (pintype "passive"))
      (node (ref "X2") (pin "6") (pinfunction "6_6") (pintype "passive"))
      (node (ref "X5") (pin "9") (pinfunction "9_9") (pintype "bidirectional"))
      (node (ref "X6") (pin "1") (pinfunction "P$1_1") (pintype "bidirectional"))
    )
    (net (code "20") (name "I2CSEC_SCL") (class "Default")
      (node (ref "R67") (pin "1") (pinfunction "1_1") (pintype "passive"))
      (node (ref "R71") (pin "1") (pinfunction "1_1") (pintype "passive"))
      (node (ref "X2") (pin "4") (pinfunction "4_4") (pintype "passive"))
    )
    (net (code "21") (name "I2CSEC_SDA") (class "Default")
      (node (ref "R63") (pin "1") (pinfunction "1_1") (pintype "passive"))
      (node (ref "R68") (pin "1") (pinfunction "1_1") (pintype "passive"))
      (node (ref "X2") (pin "5") (pinfunction "5_5") (pintype "passive"))
    )
    (net (code "22") (name "Net-(C1-Pad1)") (class "Default")
      (node (ref "C1") (pin "1") (pinfunction "1_1") (pintype "passive"))
      (node (ref "R1") (pin "2") (pinfunction "2_2") (pintype "passive"))
      (node (ref "R3") (pin "2") (pinfunction "2_2") (pintype "passive"))
    )
    (net (code "23") (name "Net-(C1-Pad2)") (class "Default")
      (node (ref "C1") (pin "2") (pinfunction "2_2") (pintype "passive"))
      (node (ref "R4") (pin "1") (pinfunction "1_1") (pintype "passive"))
      (node (ref "R5") (pin "2") (pinfunction "2_2") (pintype "passive"))
      (node (ref "TR1") (pin "B") (pinfunction "B_B") (pintype "passive"))
    )
    (net (code "24") (name "Net-(C2-Pad1)") (class "Default")
      (node (ref "C2") (pin "1") (pinfunction "1_1") (pintype "passive"))
      (node (ref "R6") (pin "2") (pinfunction "2_2") (pintype "passive"))
      (node (ref "TR1") (pin "E") (pinfunction "E_E") (pintype "passive"))
    )
    (net (code "25") (name "Net-(C3-Pad2)") (class "Default")
      (node (ref "C3") (pin "2") (pinfunction "2_2") (pintype "passive"))
      (node (ref "C4") (pin "1") (pinfunction "1_1") (pintype "passive"))
    )
    (net (code "26") (name "Net-(C4-Pad2)") (class "Default")
      (node (ref "C4") (pin "2") (pinfunction "2_2") (pintype "passive"))
      (node (ref "L4") (pin "1") (pinfunction "1_1") (pintype "passive"))
      (node (ref "TR2") (pin "B") (pinfunction "B_B") (pintype "passive"))
    )
    (net (code "27") (name "Net-(C6-Pad1)") (class "Default")
      (node (ref "C6") (pin "1") (pinfunction "1_1") (pintype "passive"))
      (node (ref "L3") (pin "2") (pinfunction "2_2") (pintype "passive"))
    )
    (net (code "28") (name "Net-(C6-Pad2)") (class "Default")
      (node (ref "C6") (pin "2") (pinfunction "2_2") (pintype "passive"))
      (node (ref "C7") (pin "1") (pinfunction "1_1") (pintype "passive"))
      (node (ref "C8") (pin "1") (pinfunction "1_1") (pintype "passive"))
      (node (ref "L5") (pin "1") (pinfunction "1_1") (pintype "passive"))
    )
    (net (code "29") (name "Net-(C10-Pad1)") (class "Default")
      (node (ref "C10") (pin "1") (pinfunction "1_1") (pintype "passive"))
      (node (ref "C8") (pin "2") (pinfunction "2_2") (pintype "passive"))
      (node (ref "C9") (pin "1") (pinfunction "1_1") (pintype "passive"))
      (node (ref "L5") (pin "2") (pinfunction "2_2") (pintype "passive"))
      (node (ref "L6") (pin "1") (pinfunction "1_1") (pintype "passive"))
    )
    (net (code "30") (name "Net-(C10-Pad2)") (class "Default")
      (node (ref "C10") (pin "2") (pinfunction "2_2") (pintype "passive"))
      (node (ref "C11") (pin "1") (pinfunction "1_1") (pintype "passive"))
      (node (ref "L6") (pin "2") (pinfunction "2_2") (pintype "passive"))
      (node (ref "X1") (pin "1") (pinfunction "1_1") (pintype "bidirectional"))
    )
    (net (code "31") (name "Net-(C16-Pad1)") (class "Default")
      (node (ref "C16") (pin "1") (pinfunction "1_1") (pintype "passive"))
      (node (ref "U5") (pin "7") (pinfunction "7_7") (pintype "output"))
    )
    (net (code "32") (name "Net-(C17-Pad1)") (class "Default")
      (node (ref "C17") (pin "1") (pinfunction "1_1") (pintype "passive"))
      (node (ref "Q2") (pin "1") (pinfunction "1_1") (pintype "passive"))
      (node (ref "U5") (pin "8") (pinfunction "8_8") (pintype "input"))
    )
    (net (code "33") (name "Net-(C18-Pad1)") (class "Default")
      (node (ref "C18") (pin "1") (pinfunction "1_1") (pintype "passive"))
      (node (ref "Q2") (pin "2") (pinfunction "2_2") (pintype "passive"))
      (node (ref "U5") (pin "9") (pinfunction "9_9") (pintype "bidirectional"))
    )
    (net (code "34") (name "Net-(C22-Pad2)") (class "Default")
      (node (ref "C22") (pin "2") (pinfunction "2_2") (pintype "passive"))
      (node (ref "C54") (pin "1") (pinfunction "1_1") (pintype "passive"))
      (node (ref "L8") (pin "1") (pinfunction "1_1") (pintype "passive"))
    )
    (net (code "35") (name "Net-(C55-Pad1)") (class "Default")
      (node (ref "C55") (pin "1") (pinfunction "1_1") (pintype "passive"))
      (node (ref "L8") (pin "2") (pinfunction "2_2") (pintype "passive"))
      (node (ref "L9") (pin "1") (pinfunction "1_1") (pintype "passive"))
    )
    (net (code "36") (name "Net-(C56-Pad1)") (class "Default")
      (node (ref "C56") (pin "1") (pinfunction "1_1") (pintype "passive"))
      (node (ref "L9") (pin "2") (pinfunction "2_2") (pintype "passive"))
      (node (ref "R1") (pin "1") (pinfunction "1_1") (pintype "passive"))
      (node (ref "R2") (pin "2") (pinfunction "2_2") (pintype "passive"))
    )
    (net (code "37") (name "Net-(C63-Pad2)") (class "Default")
      (node (ref "C63") (pin "2") (pinfunction "2_2") (pintype "passive"))
      (node (ref "R28") (pin "2") (pinfunction "2_2") (pintype "passive"))
    )
    (net (code "38") (name "Net-(C69-Pad1)") (class "Default")
      (node (ref "C69") (pin "1") (pinfunction "1_1") (pintype "passive"))
      (node (ref "R32") (pin "1") (pinfunction "1_1") (pintype "passive"))
    )
    (net (code "39") (name "Net-(D1-A1)") (class "Default")
      (node (ref "C5") (pin "1") (pinfunction "1_1") (pintype "passive"))
      (node (ref "D1") (pin "1") (pinfunction "A1_1") (pintype "passive"))
      (node (ref "L4") (pin "2") (pinfunction "2_2") (pintype "passive"))
      (node (ref "R7") (pin "1") (pinfunction "1_1") (pintype "passive"))
    )
    (net (code "40") (name "Net-(L1-1)") (class "Default")
      (node (ref "L1") (pin "P$1") (pinfunction "1_P$1") (pintype "passive"))
      (node (ref "R9") (pin "1") (pinfunction "1_1") (pintype "passive"))
    )
    (net (code "41") (name "Net-(L1-2)") (class "Default")
      (node (ref "C3") (pin "1") (pinfunction "1_1") (pintype "passive"))
      (node (ref "L1") (pin "P$2") (pinfunction "2_P$2") (pintype "passive"))
      (node (ref "TR1") (pin "C") (pinfunction "C_C") (pintype "passive"))
    )
    (net (code "42") (name "Net-(L2-1)") (class "Default")
      (node (ref "L2") (pin "P$1") (pinfunction "1_P$1") (pintype "passive"))
      (node (ref "R11") (pin "1") (pinfunction "1_1") (pintype "passive"))
    )
    (net (code "43") (name "Net-(L2-2)") (class "Default")
      (node (ref "L2") (pin "P$2") (pinfunction "2_P$2") (pintype "passive"))
      (node (ref "L3") (pin "1") (pinfunction "1_1") (pintype "passive"))
      (node (ref "TR2") (pin "C") (pinfunction "C_C") (pintype "passive"))
    )
    (net (code "44") (name "Net-(LED1-PadA)") (class "Default")
      (node (ref "LED1") (pin "A") (pinfunction "A_A") (pintype "passive"))
      (node (ref "R33") (pin "2") (pinfunction "2_2") (pintype "passive"))
    )
    (net (code "45") (name "Net-(R4-Pad2)") (class "Default")
      (node (ref "R4") (pin "2") (pinfunction "2_2") (pintype "passive"))
      (node (ref "R8") (pin "1") (pinfunction "1_1") (pintype "passive"))
    )
    (net (code "46") (name "Net-(R10-Pad1)") (class "Default")
      (node (ref "R10") (pin "1") (pinfunction "1_1") (pintype "passive"))
      (node (ref "R7") (pin "2") (pinfunction "2_2") (pintype "passive"))
    )
    (net (code "47") (name "Net-(R16-Pad1)") (class "Default")
      (node (ref "R16") (pin "1") (pinfunction "1_1") (pintype "passive"))
      (node (ref "X5") (pin "10") (pinfunction "10_10") (pintype "bidirectional"))
    )
    (net (code "48") (name "Net-(R26-Pad2)") (class "Default")
      (node (ref "R26") (pin "2") (pinfunction "2_2") (pintype "passive"))
      (node (ref "U5") (pin "31") (pinfunction "31_31") (pintype "bidirectional"))
    )
    (net (code "49") (name "Net-(R27-Pad2)") (class "Default")
      (node (ref "R27") (pin "2") (pinfunction "2_2") (pintype "passive"))
      (node (ref "U5") (pin "29") (pinfunction "29_29") (pintype "bidirectional"))
    )
    (net (code "50") (name "Net-(R33-Pad1)") (class "Default")
      (node (ref "R33") (pin "1") (pinfunction "1_1") (pintype "passive"))
      (node (ref "U5") (pin "13") (pinfunction "13_13") (pintype "bidirectional"))
    )
    (net (code "51") (name "Net-(R63-Pad2)") (class "Default")
      (node (ref "R63") (pin "2") (pinfunction "2_2") (pintype "passive"))
      (node (ref "U5") (pin "32") (pinfunction "32_32") (pintype "bidirectional"))
    )
    (net (code "52") (name "Net-(R67-Pad2)") (class "Default")
      (node (ref "R67") (pin "2") (pinfunction "2_2") (pintype "passive"))
      (node (ref "U5") (pin "33") (pinfunction "33_33") (pintype "bidirectional"))
    )
    (net (code "53") (name "Net-(TCXO1-P$3)") (class "Default")
      (node (ref "C77") (pin "1") (pinfunction "1_1") (pintype "passive"))
      (node (ref "TCXO1") (pin "3") (pinfunction "P$3_3") (pintype "bidirectional"))
    )
    (net (code "54") (name "Net-(TR3-D)") (class "Default")
      (node (ref "C23") (pin "1") (pinfunction "1_1") (pintype "passive"))
      (node (ref "R12") (pin "1") (pinfunction "1_1") (pintype "passive"))
      (node (ref "TR3") (pin "3") (pinfunction "D_3") (pintype "bidirectional"))
      (node (ref "U2") (pin "3") (pinfunction "P$3_3") (pintype "input"))
    )
    (net (code "55") (name "Net-(U1-P$1)") (class "Default")
      (node (ref "C24") (pin "1") (pinfunction "1_1") (pintype "passive"))
      (node (ref "U1") (pin "1") (pinfunction "P$1_1") (pintype "input"))
      (node (ref "U1") (pin "2") (pinfunction "P$2_2") (pintype "power_in"))
      (node (ref "U2") (pin "6") (pinfunction "P$6_6") (pintype "output"))
      (node (ref "U2") (pin "7") (pinfunction "P$7_7") (pintype "output"))
    )
    (net (code "56") (name "Net-(U1-P$5)") (class "Default")
      (node (ref "C25") (pin "1") (pinfunction "1_1") (pintype "passive"))
      (node (ref "R14") (pin "2") (pinfunction "2_2") (pintype "passive"))
      (node (ref "R15") (pin "1") (pinfunction "1_1") (pintype "passive"))
      (node (ref "U1") (pin "5") (pinfunction "P$5_5") (pintype "input"))
    )
    (net (code "57") (name "Net-(U2-P$5)") (class "Default")
      (node (ref "R13") (pin "2") (pinfunction "2_2") (pintype "passive"))
      (node (ref "U2") (pin "5") (pinfunction "P$5_5") (pintype "passive"))
    )
    (net (code "58") (name "Net-(U3-P$5)") (class "Default")
      (node (ref "R17") (pin "2") (pinfunction "2_2") (pintype "passive"))
      (node (ref "U3") (pin "5") (pinfunction "P$5_5") (pintype "passive"))
    )
    (net (code "59") (name "Net-(U3-P$6)") (class "Default")
      (node (ref "C20") (pin "1") (pinfunction "1_1") (pintype "passive"))
      (node (ref "C35") (pin "1") (pinfunction "1_1") (pintype "passive"))
      (node (ref "U12") (pin "1") (pinfunction "1_1") (pintype "power_in"))
      (node (ref "U12") (pin "3") (pinfunction "3_3") (pintype "input"))
      (node (ref "U3") (pin "6") (pinfunction "P$6_6") (pintype "output"))
      (node (ref "U3") (pin "7") (pinfunction "P$7_7") (pintype "output"))
    )
    (net (code "60") (name "Net-(U4A-+IN)") (class "Default")
      (node (ref "C12") (pin "1") (pinfunction "1_1") (pintype "passive"))
      (node (ref "R20") (pin "1") (pinfunction "1_1") (pintype "passive"))
      (node (ref "R22") (pin "2") (pinfunction "2_2") (pintype "passive"))
      (node (ref "U4") (pin "3") (pinfunction "+IN_3") (pintype "input"))
    )
    (net (code "61") (name "Net-(U4B-+IN)") (class "Default")
      (node (ref "C13") (pin "1") (pinfunction "1_1") (pintype "passive"))
      (node (ref "R21") (pin "1") (pinfunction "1_1") (pintype "passive"))
      (node (ref "R23") (pin "2") (pinfunction "2_2") (pintype "passive"))
      (node (ref "U4") (pin "5") (pinfunction "+IN_5") (pintype "input"))
    )
    (net (code "62") (name "Net-(U5-Pad54)") (class "Default")
      (node (ref "U5") (pin "54") (pinfunction "54_54") (pintype "bidirectional"))
      (node (ref "X5") (pin "1") (pinfunction "1_1") (pintype "bidirectional"))
    )
    (net (code "63") (name "Net-(U5-Pad55)") (class "Default")
      (node (ref "U5") (pin "55") (pinfunction "55_55") (pintype "input"))
      (node (ref "X5") (pin "3") (pinfunction "3_3") (pintype "bidirectional"))
    )
    (net (code "64") (name "Net-(U5-Pad56)") (class "Default")
      (node (ref "U5") (pin "56") (pinfunction "56_56") (pintype "input"))
      (node (ref "X5") (pin "5") (pinfunction "5_5") (pintype "bidirectional"))
    )
    (net (code "65") (name "Net-(U5-Pad57)") (class "Default")
      (node (ref "U5") (pin "57") (pinfunction "57_57") (pintype "input"))
      (node (ref "X5") (pin "7") (pinfunction "7_7") (pintype "bidirectional"))
    )
    (net (code "66") (name "Net-(U6-P$2)") (class "Default")
      (node (ref "C62") (pin "2") (pinfunction "2_2") (pintype "passive"))
      (node (ref "C63") (pin "1") (pinfunction "1_1") (pintype "passive"))
      (node (ref "U6") (pin "2") (pinfunction "P$2_2") (pintype "bidirectional"))
    )
    (net (code "67") (name "Net-(U6-P$8)") (class "Default")
      (node (ref "R24") (pin "2") (pinfunction "2_2") (pintype "passive"))
      (node (ref "U6") (pin "8") (pinfunction "P$8_8") (pintype "bidirectional"))
    )
    (net (code "68") (name "Net-(U6-P$10)") (class "Default")
      (node (ref "R25") (pin "2") (pinfunction "2_2") (pintype "passive"))
      (node (ref "U6") (pin "10") (pinfunction "P$10_10") (pintype "bidirectional"))
    )
    (net (code "69") (name "Net-(U6-P$11)") (class "Default")
      (node (ref "C67") (pin "1") (pinfunction "1_1") (pintype "passive"))
      (node (ref "U6") (pin "11") (pinfunction "P$11_11") (pintype "bidirectional"))
    )
    (net (code "70") (name "Net-(U6-P$31)") (class "Default")
      (node (ref "C60") (pin "1") (pinfunction "1_1") (pintype "passive"))
      (node (ref "U6") (pin "31") (pinfunction "P$31_31") (pintype "bidirectional"))
    )
    (net (code "71") (name "Net-(U6-P$41)") (class "Default")
      (node (ref "C58") (pin "1") (pinfunction "1_1") (pintype "passive"))
      (node (ref "U6") (pin "41") (pinfunction "P$41_41") (pintype "bidirectional"))
    )
    (net (code "72") (name "Net-(U6-P$44)") (class "Default")
      (node (ref "L10") (pin "2") (pinfunction "2_2") (pintype "passive"))
      (node (ref "U6") (pin "44") (pinfunction "P$44_44") (pintype "bidirectional"))
    )
    (net (code "73") (name "Net-(U6-P$46)") (class "Default")
      (node (ref "L10") (pin "1") (pinfunction "1_1") (pintype "passive"))
      (node (ref "U6") (pin "46") (pinfunction "P$46_46") (pintype "bidirectional"))
    )
    (net (code "74") (name "Net-(U6-P$48)") (class "Default")
      (node (ref "C62") (pin "1") (pinfunction "1_1") (pintype "passive"))
      (node (ref "U6") (pin "48") (pinfunction "P$48_48") (pintype "bidirectional"))
    )
    (net (code "75") (name "PA_-FAULT") (class "Default")
      (node (ref "R34") (pin "1") (pinfunction "1_1") (pintype "passive"))
      (node (ref "U2") (pin "8") (pinfunction "P$8_8") (pintype "output"))
      (node (ref "U5") (pin "28") (pinfunction "28_28") (pintype "bidirectional"))
    )
    (net (code "76") (name "PA_ON") (class "Default")
      (node (ref "TR3") (pin "1") (pinfunction "G_1") (pintype "bidirectional"))
      (node (ref "U5") (pin "27") (pinfunction "27_27") (pintype "bidirectional"))
    )
    (net (code "77") (name "RESETBEACON") (class "Default")
      (node (ref "R16") (pin "2") (pinfunction "2_2") (pintype "passive"))
      (node (ref "R19") (pin "1") (pinfunction "1_1") (pintype "passive"))
      (node (ref "U5") (pin "58") (pinfunction "58_58") (pintype "input"))
      (node (ref "U7") (pin "4") (pinfunction "P$4_4") (pintype "output"))
    )
    (net (code "78") (name "RXD") (class "Default")
      (node (ref "U5") (pin "35") (pinfunction "35_35") (pintype "bidirectional"))
      (node (ref "X3") (pin "1") (pinfunction "P$1_1") (pintype "bidirectional"))
    )
    (net (code "79") (name "TXD") (class "Default")
      (node (ref "U5") (pin "34") (pinfunction "34_34") (pintype "bidirectional"))
      (node (ref "X4") (pin "1") (pinfunction "P$1_1") (pintype "bidirectional"))
    )
    (net (code "80") (name "VBEACON_PA") (class "Default")
      (node (ref "C26") (pin "1") (pinfunction "1_1") (pintype "passive"))
      (node (ref "C30") (pin "P$1") (pinfunction "1_P$1") (pintype "passive"))
      (node (ref "R10") (pin "2") (pinfunction "2_2") (pintype "passive"))
      (node (ref "R11") (pin "2") (pinfunction "2_2") (pintype "passive"))
      (node (ref "R14") (pin "1") (pinfunction "1_1") (pintype "passive"))
      (node (ref "R22") (pin "1") (pinfunction "1_1") (pintype "passive"))
      (node (ref "R8") (pin "2") (pinfunction "2_2") (pintype "passive"))
      (node (ref "R9") (pin "2") (pinfunction "2_2") (pintype "passive"))
      (node (ref "U1") (pin "4") (pinfunction "P$4_4") (pintype "power_in"))
    )
    (net (code "81") (name "VBUS") (class "Default")
      (node (ref "R12") (pin "2") (pinfunction "2_2") (pintype "passive"))
      (node (ref "R23") (pin "1") (pinfunction "1_1") (pintype "passive"))
      (node (ref "U2") (pin "1") (pinfunction "P$1_1") (pintype "input"))
      (node (ref "U2") (pin "2") (pinfunction "P$2_2") (pintype "input"))
      (node (ref "U3") (pin "1") (pinfunction "P$1_1") (pintype "input"))
      (node (ref "U3") (pin "2") (pinfunction "P$2_2") (pintype "input"))
      (node (ref "X2") (pin "10") (pinfunction "10_10") (pintype "passive"))
      (node (ref "X2") (pin "9") (pinfunction "9_9") (pintype "passive"))
    )
    (net (code "82") (name "VCCRF") (class "Default")
      (node (ref "C28") (pin "1") (pinfunction "1_1") (pintype "passive"))
      (node (ref "C51") (pin "1") (pinfunction "1_1") (pintype "passive"))
      (node (ref "C52") (pin "1") (pinfunction "1_1") (pintype "passive"))
      (node (ref "C57") (pin "1") (pinfunction "1_1") (pintype "passive"))
      (node (ref "C59") (pin "1") (pinfunction "1_1") (pintype "passive"))
      (node (ref "C61") (pin "1") (pinfunction "1_1") (pintype "passive"))
      (node (ref "C64") (pin "1") (pinfunction "1_1") (pintype "passive"))
      (node (ref "C65") (pin "1") (pinfunction "1_1") (pintype "passive"))
      (node (ref "C66") (pin "1") (pinfunction "1_1") (pintype "passive"))
      (node (ref "C76") (pin "1") (pinfunction "1_1") (pintype "passive"))
      (node (ref "L11") (pin "2") (pinfunction "2_2") (pintype "passive"))
      (node (ref "L7") (pin "2") (pinfunction "2_2") (pintype "passive"))
      (node (ref "TCXO1") (pin "4") (pinfunction "P$4_4") (pintype "bidirectional"))
      (node (ref "U6") (pin "3") (pinfunction "P$3_3") (pintype "bidirectional"))
      (node (ref "U6") (pin "32") (pinfunction "P$32_32") (pintype "bidirectional"))
      (node (ref "U6") (pin "40") (pinfunction "P$40_40") (pintype "bidirectional"))
      (node (ref "U6") (pin "43") (pinfunction "P$43_43") (pintype "bidirectional"))
      (node (ref "U6") (pin "9") (pinfunction "P$9_9") (pintype "bidirectional"))
    )
    (net (code "83") (name "unconnected-(D1-C2-Pad2)") (class "Default")
      (node (ref "D1") (pin "2") (pinfunction "C2_2") (pintype "passive"))
    )
    (net (code "84") (name "unconnected-(H1-MOUNT-PadB3,2)") (class "Default")
      (node (ref "H1") (pin "B3,2") (pinfunction "MOUNT_B3,2") (pintype "passive"))
    )
    (net (code "85") (name "unconnected-(H2-MOUNT-PadB3,2)") (class "Default")
      (node (ref "H2") (pin "B3,2") (pinfunction "MOUNT_B3,2") (pintype "passive"))
    )
    (net (code "86") (name "unconnected-(H3-MOUNT-PadB3,2)") (class "Default")
      (node (ref "H3") (pin "B3,2") (pinfunction "MOUNT_B3,2") (pintype "passive"))
    )
    (net (code "87") (name "unconnected-(H4-MOUNT-PadB3,2)") (class "Default")
      (node (ref "H4") (pin "B3,2") (pinfunction "MOUNT_B3,2") (pintype "passive"))
    )
    (net (code "88") (name "unconnected-(U5-Pad2)") (class "Default")
      (node (ref "U5") (pin "2") (pinfunction "2_2") (pintype "bidirectional"))
    )
    (net (code "89") (name "unconnected-(U5-Pad3)") (class "Default")
      (node (ref "U5") (pin "3") (pinfunction "3_3") (pintype "bidirectional"))
    )
    (net (code "90") (name "unconnected-(U5-Pad4)") (class "Default")
      (node (ref "U5") (pin "4") (pinfunction "4_4") (pintype "bidirectional"))
    )
    (net (code "91") (name "unconnected-(U5-Pad5)") (class "Default")
      (node (ref "U5") (pin "5") (pinfunction "5_5") (pintype "bidirectional"))
    )
    (net (code "92") (name "unconnected-(U5-Pad6)") (class "Default")
      (node (ref "U5") (pin "6") (pinfunction "6_6") (pintype "bidirectional"))
    )
    (net (code "93") (name "unconnected-(U5-Pad10)") (class "Default")
      (node (ref "U5") (pin "10") (pinfunction "10_10") (pintype "input"))
    )
    (net (code "94") (name "unconnected-(U5-Pad12)") (class "Default")
      (node (ref "U5") (pin "12") (pinfunction "12_12") (pintype "bidirectional"))
    )
    (net (code "95") (name "unconnected-(U5-Pad14)") (class "Default")
      (node (ref "U5") (pin "14") (pinfunction "14_14") (pintype "bidirectional"))
    )
    (net (code "96") (name "unconnected-(U5-Pad15)") (class "Default")
      (node (ref "U5") (pin "15") (pinfunction "15_15") (pintype "bidirectional"))
    )
    (net (code "97") (name "unconnected-(U5-Pad16)") (class "Default")
      (node (ref "U5") (pin "16") (pinfunction "16_16") (pintype "bidirectional"))
    )
    (net (code "98") (name "unconnected-(U5-Pad17)") (class "Default")
      (node (ref "U5") (pin "17") (pinfunction "17_17") (pintype "bidirectional"))
    )
    (net (code "99") (name "unconnected-(U5-Pad18)") (class "Default")
      (node (ref "U5") (pin "18") (pinfunction "18_18") (pintype "bidirectional"))
    )
    (net (code "100") (name "unconnected-(U5-Pad19)") (class "Default")
      (node (ref "U5") (pin "19") (pinfunction "19_19") (pintype "bidirectional"))
    )
    (net (code "101") (name "unconnected-(U5-Pad30)") (class "Default")
      (node (ref "U5") (pin "30") (pinfunction "30_30") (pintype "bidirectional"))
    )
    (net (code "102") (name "unconnected-(U5-Pad36)") (class "Default")
      (node (ref "U5") (pin "36") (pinfunction "36_36") (pintype "output"))
    )
    (net (code "103") (name "unconnected-(U5-Pad37)") (class "Default")
      (node (ref "U5") (pin "37") (pinfunction "37_37") (pintype "bidirectional"))
    )
    (net (code "104") (name "unconnected-(U5-Pad38)") (class "Default")
      (node (ref "U5") (pin "38") (pinfunction "38_38") (pintype "bidirectional"))
    )
    (net (code "105") (name "unconnected-(U5-Pad39)") (class "Default")
      (node (ref "U5") (pin "39") (pinfunction "39_39") (pintype "bidirectional"))
    )
    (net (code "106") (name "unconnected-(U5-Pad40)") (class "Default")
      (node (ref "U5") (pin "40") (pinfunction "40_40") (pintype "input"))
    )
    (net (code "107") (name "unconnected-(U5-Pad41)") (class "Default")
      (node (ref "U5") (pin "41") (pinfunction "41_41") (pintype "bidirectional"))
    )
    (net (code "108") (name "unconnected-(U5-Pad42)") (class "Default")
      (node (ref "U5") (pin "42") (pinfunction "42_42") (pintype "bidirectional"))
    )
    (net (code "109") (name "unconnected-(U5-Pad43)") (class "Default")
      (node (ref "U5") (pin "43") (pinfunction "43_43") (pintype "bidirectional"))
    )
    (net (code "110") (name "unconnected-(U5-Pad44)") (class "Default")
      (node (ref "U5") (pin "44") (pinfunction "44_44") (pintype "bidirectional"))
    )
    (net (code "111") (name "unconnected-(U5-Pad45)") (class "Default")
      (node (ref "U5") (pin "45") (pinfunction "45_45") (pintype "bidirectional"))
    )
    (net (code "112") (name "unconnected-(U5-Pad46)") (class "Default")
      (node (ref "U5") (pin "46") (pinfunction "46_46") (pintype "bidirectional"))
    )
    (net (code "113") (name "unconnected-(U5-Pad47)") (class "Default")
      (node (ref "U5") (pin "47") (pinfunction "47_47") (pintype "bidirectional"))
    )
    (net (code "114") (name "unconnected-(U5-Pad48)") (class "Default")
      (node (ref "U5") (pin "48") (pinfunction "48_48") (pintype "bidirectional"))
    )
    (net (code "115") (name "unconnected-(U5-Pad49)") (class "Default")
      (node (ref "U5") (pin "49") (pinfunction "49_49") (pintype "bidirectional"))
    )
    (net (code "116") (name "unconnected-(U5-Pad50)") (class "Default")
      (node (ref "U5") (pin "50") (pinfunction "50_50") (pintype "bidirectional"))
    )
    (net (code "117") (name "unconnected-(U5-Pad51)") (class "Default")
      (node (ref "U5") (pin "51") (pinfunction "51_51") (pintype "bidirectional"))
    )
    (net (code "118") (name "unconnected-(U5-Pad52)") (class "Default")
      (node (ref "U5") (pin "52") (pinfunction "52_52") (pintype "output"))
    )
    (net (code "119") (name "unconnected-(U5-Pad61)") (class "Default")
      (node (ref "U5") (pin "61") (pinfunction "61_61") (pintype "bidirectional"))
    )
    (net (code "120") (name "unconnected-(U6-P$13-Pad13)") (class "Default")
      (node (ref "U6") (pin "13") (pinfunction "P$13_13") (pintype "bidirectional"))
    )
    (net (code "121") (name "unconnected-(U6-P$14-Pad14)") (class "Default")
      (node (ref "U6") (pin "14") (pinfunction "P$14_14") (pintype "bidirectional"))
    )
    (net (code "122") (name "unconnected-(U6-P$15-Pad15)") (class "Default")
      (node (ref "U6") (pin "15") (pinfunction "P$15_15") (pintype "bidirectional"))
    )
    (net (code "123") (name "unconnected-(U6-P$16-Pad16)") (class "Default")
      (node (ref "U6") (pin "16") (pinfunction "P$16_16") (pintype "bidirectional"))
    )
    (net (code "124") (name "unconnected-(U6-P$17-Pad17)") (class "Default")
      (node (ref "U6") (pin "17") (pinfunction "P$17_17") (pintype "bidirectional"))
    )
    (net (code "125") (name "unconnected-(U6-P$18-Pad18)") (class "Default")
      (node (ref "U6") (pin "18") (pinfunction "P$18_18") (pintype "bidirectional"))
    )
    (net (code "126") (name "unconnected-(U6-P$20-Pad20)") (class "Default")
      (node (ref "U6") (pin "20") (pinfunction "P$20_20") (pintype "bidirectional"))
    )
    (net (code "127") (name "unconnected-(U6-P$21-Pad21)") (class "Default")
      (node (ref "U6") (pin "21") (pinfunction "P$21_21") (pintype "bidirectional"))
    )
    (net (code "128") (name "unconnected-(U6-P$23-Pad23)") (class "Default")
      (node (ref "U6") (pin "23") (pinfunction "P$23_23") (pintype "bidirectional"))
    )
    (net (code "129") (name "unconnected-(U6-P$30-Pad30)") (class "Default")
      (node (ref "U6") (pin "30") (pinfunction "P$30_30") (pintype "bidirectional"))
    )
    (net (code "130") (name "unconnected-(U6-P$33-Pad33)") (class "Default")
      (node (ref "U6") (pin "33") (pinfunction "P$33_33") (pintype "bidirectional"))
    )
    (net (code "131") (name "unconnected-(U6-P$36-Pad36)") (class "Default")
      (node (ref "U6") (pin "36") (pinfunction "P$36_36") (pintype "bidirectional"))
    )
    (net (code "132") (name "unconnected-(U6-P$37-Pad37)") (class "Default")
      (node (ref "U6") (pin "37") (pinfunction "P$37_37") (pintype "bidirectional"))
    )
    (net (code "133") (name "unconnected-(U6-P$38-Pad38)") (class "Default")
      (node (ref "U6") (pin "38") (pinfunction "P$38_38") (pintype "bidirectional"))
    )
    (net (code "134") (name "unconnected-(U7-P$3-Pad3)") (class "Default")
      (node (ref "U7") (pin "3") (pinfunction "P$3_3") (pintype "input"))
    )
    (net (code "135") (name "unconnected-(U12-Pad4)") (class "Default")
      (node (ref "U12") (pin "4") (pinfunction "4_4") (pintype "passive"))
    )
    (net (code "136") (name "unconnected-(X5-Pad2)") (class "Default")
      (node (ref "X5") (pin "2") (pinfunction "2_2") (pintype "bidirectional"))
    )
    (net (code "137") (name "unconnected-(X5-Pad6)") (class "Default")
      (node (ref "X5") (pin "6") (pinfunction "6_6") (pintype "bidirectional"))
    )
    (net (code "138") (name "unconnected-(X5-Pad8)") (class "Default")
      (node (ref "X5") (pin "8") (pinfunction "8_8") (pintype "bidirectional"))
    )
  )
)
